# Powerboost.net
KiCad netlist of a schematic drawn in Altium Designer
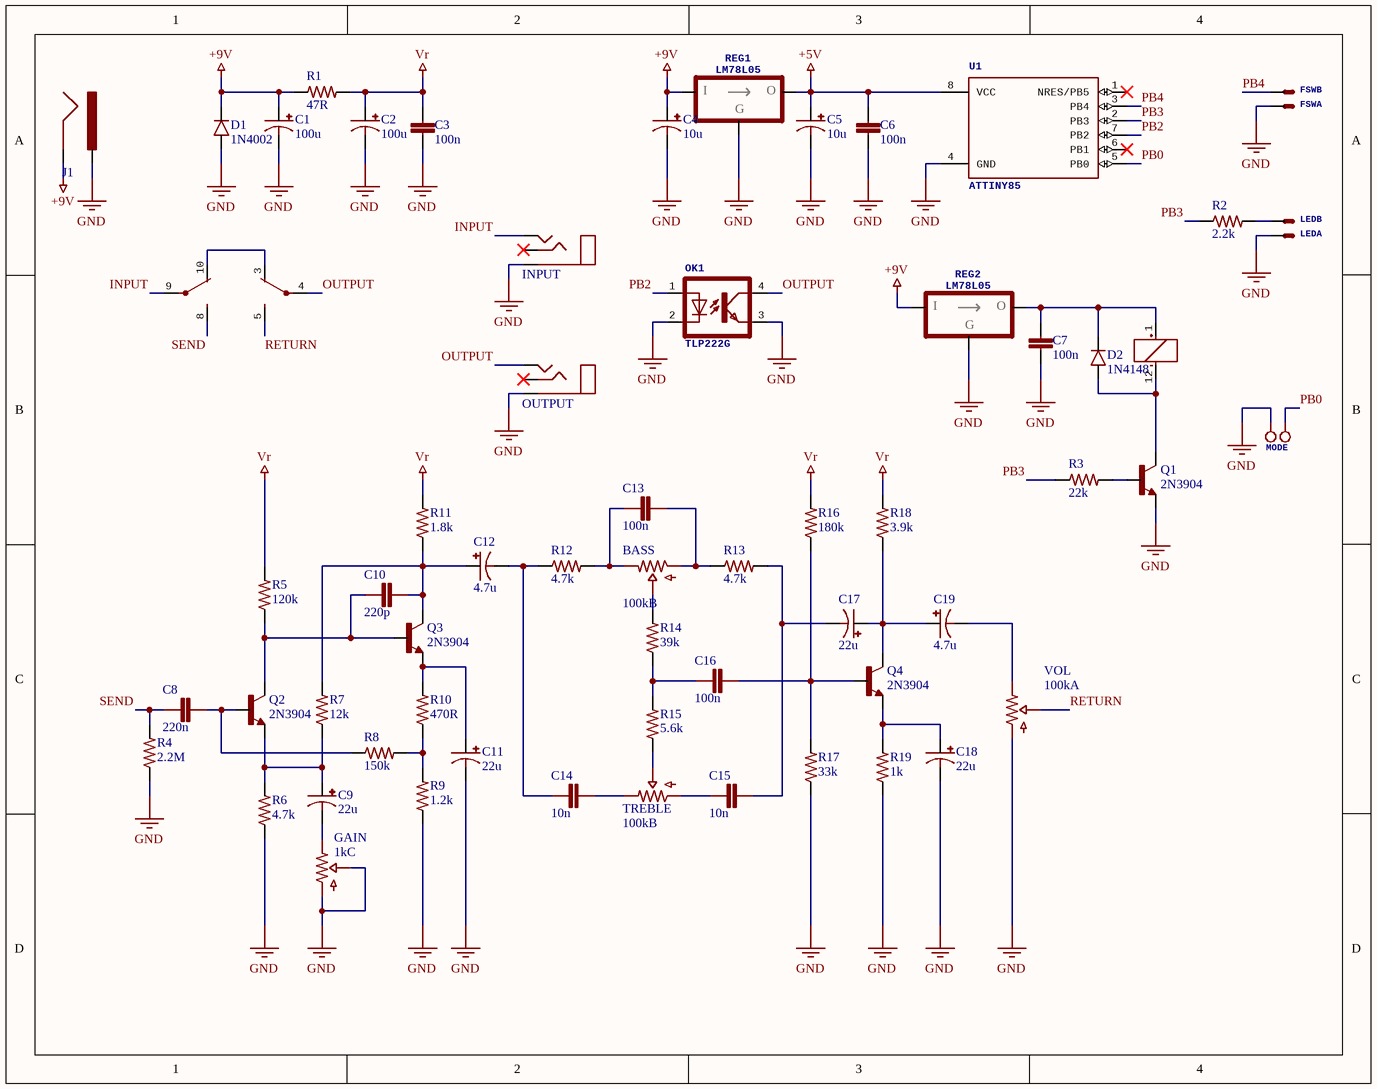
[diagram p0: Powerboost.SchDoc]

(export (version "E")
  (design (tool "Eeschema 10.0.6"))
  (components
    (comp (ref "BASS")
      (value "100kB")
      (footprint "ALPHA_16mm_BOTTOM")
      (description "100k Lin potentiometer round shaft")
      (libsource (lib "Pedals") (part "100kB_ALPHA_16mm"))
    )
    (comp (ref "C1")
      (value "100u")
      (footprint "ELEC_063_025")
      (description "100u 25V electrolytic capacitor")
      (libsource (lib "Pedals") (part "ELEC_100u_25V"))
    )
    (comp (ref "C2")
      (value "100u")
      (footprint "ELEC_063_025")
      (description "100u 25V electrolytic capacitor")
      (libsource (lib "Pedals") (part "ELEC_100u_25V"))
    )
    (comp (ref "C3")
      (value "100n")
      (footprint "CER_050")
      (description "100n MLCC X7R radial capacitor")
      (libsource (lib "") (part "CER_100n_1"))
    )
    (comp (ref "C4")
      (value "10u")
      (footprint "ELEC_040_020")
      (description "10u 50V electrolytic capacitor")
      (libsource (lib "Pedals") (part "ELEC_10u_50V"))
    )
    (comp (ref "C5")
      (value "10u")
      (footprint "ELEC_040_020")
      (description "10u 50V electrolytic capacitor")
      (libsource (lib "Pedals") (part "ELEC_10u_50V"))
    )
    (comp (ref "C6")
      (value "100n")
      (footprint "CER_050")
      (description "100n MLCC X7R radial capacitor")
      (libsource (lib "Pedals") (part "CER_100n"))
    )
    (comp (ref "C7")
      (value "100n")
      (footprint "CER_050")
      (description "100n MLCC X7R radial capacitor")
      (libsource (lib "") (part "CER_100n_1"))
    )
    (comp (ref "C8")
      (value "220n")
      (footprint "FILMBOX_SMALL")
      (description "220n 100V polyester film box capacitor")
      (libsource (lib "Pedals") (part "FILMBOX_220n"))
    )
    (comp (ref "C9")
      (value "22u")
      (footprint "ELEC_LESR_050_020")
      (description "22u 50V Low ESR ectrolytic capacitor")
      (libsource (lib "Pedals") (part "ELEC_LESR_22u_50V"))
    )
    (comp (ref "C10")
      (value "220p")
      (footprint "CER_050")
      (description "220p MLCC X7R radial capacitor")
      (libsource (lib "Pedals") (part "CER_220p"))
    )
    (comp (ref "C11")
      (value "22u")
      (footprint "ELEC_LESR_050_020")
      (description "22u 50V Low ESR ectrolytic capacitor")
      (libsource (lib "Pedals") (part "ELEC_LESR_22u_50V"))
    )
    (comp (ref "C12")
      (value "4.7u")
      (footprint "ELEC_LESR_050_020")
      (description "4.7u 50V Low ESR ectrolytic capacitor")
      (libsource (lib "Pedals") (part "ELEC_LESR_4.7u_50V"))
    )
    (comp (ref "C13")
      (value "100n")
      (footprint "FILMBOX_SMALL")
      (description "100n 100V polyester film box capacitor")
      (libsource (lib "Pedals") (part "FILMBOX_100n"))
    )
    (comp (ref "C14")
      (value "10n")
      (footprint "FILMBOX_SMALL")
      (description "10n 100V polyester film box capacitor")
      (libsource (lib "Pedals") (part "FILMBOX_10n"))
    )
    (comp (ref "C15")
      (value "10n")
      (footprint "FILMBOX_SMALL")
      (description "10n 100V polyester film box capacitor")
      (libsource (lib "Pedals") (part "FILMBOX_10n"))
    )
    (comp (ref "C16")
      (value "100n")
      (footprint "FILMBOX_SMALL")
      (description "100n 100V polyester film box capacitor")
      (libsource (lib "Pedals") (part "FILMBOX_100n"))
    )
    (comp (ref "C17")
      (value "22u")
      (footprint "ELEC_LESR_050_020")
      (description "22u 50V Low ESR ectrolytic capacitor")
      (libsource (lib "") (part "ELEC_LESR_22u_50V_1"))
    )
    (comp (ref "C18")
      (value "22u")
      (footprint "ELEC_LESR_050_020")
      (description "22u 50V Low ESR ectrolytic capacitor")
      (libsource (lib "Pedals") (part "ELEC_LESR_22u_50V"))
    )
    (comp (ref "C19")
      (value "4.7u")
      (footprint "ELEC_LESR_050_020")
      (description "4.7u 50V Low ESR ectrolytic capacitor")
      (libsource (lib "Pedals") (part "ELEC_LESR_4.7u_50V"))
    )
    (comp (ref "D1") (value "1N4002") (footprint "DO41_2") (libsource (lib "Pedals") (part "1N4002")))
    (comp (ref "D2") (value "1N4148") (footprint "DO35_2") (libsource (lib "Pedals") (part "1N4148")))
    (comp (ref "FSW")
      (value "~")
      (footprint "JST-XH-02")
      (description "2 Pins male XH header")
      (libsource (lib "Pedals") (part "JST-XH-02"))
    )
    (comp (ref "GAIN")
      (value "1kC")
      (footprint "ALPHA_16mm_BOTTOM")
      (description "1k Reverse log potentiometer round shaft")
      (libsource (lib "Pedals") (part "1kC_ALPHA_16mm"))
    )
    (comp (ref "INPUT")
      (value "~")
      (footprint "STEREO")
      (description "6.35mm stereo insulated socket jack PCB mounted")
      (libsource (lib "Pedals") (part "STEREO"))
    )
    (comp (ref "J1")
      (value "DC_JACK")
      (footprint "DC_JACK")
      (description "DC Power jack 2.1mm barrel")
      (libsource (lib "Pedals") (part "DC_JACK"))
    )
    (comp (ref "K1")
      (value "~")
      (footprint "NA5")
      (description "NA5W-K")
      (libsource (lib "") (part "NA5W-K_2"))
    )
    (comp (ref "LED")
      (value "JST-XH-02")
      (footprint "JST-XH-02")
      (description "2 Pins male XH header")
      (libsource (lib "Pedals") (part "JST-XH-02"))
    )
    (comp (ref "MODE")
      (value "HEADER_2PINS")
      (footprint "HEADER_2PINS")
      (description "2 Pins male header")
      (libsource (lib "Pedals") (part "HEADER_2PINS"))
    )
    (comp (ref "OK1") (value "TLP222G") (footprint "DIL4") (libsource (lib "Pedals") (part "TLP222G")))
    (comp (ref "OUTPUT")
      (value "~")
      (footprint "STEREO")
      (description "6.35mm stereo insulated socket jack PCB mounted")
      (libsource (lib "Pedals") (part "STEREO"))
    )
    (comp (ref "Q1") (value "2N3904") (footprint "TO92") (libsource (lib "Pedals") (part "2N3904")))
    (comp (ref "Q2") (value "2N3904") (footprint "TO92") (libsource (lib "Pedals") (part "2N3904")))
    (comp (ref "Q3") (value "2N3904") (footprint "TO92") (libsource (lib "Pedals") (part "2N3904")))
    (comp (ref "Q4") (value "2N3904") (footprint "TO92") (libsource (lib "Pedals") (part "2N3904")))
    (comp (ref "R1")
      (value "47R")
      (footprint "R_3_47R_025W")
      (description "47R metal film 1/4W Resistor")
      (libsource (lib "Pedals") (part "R_3_47R_025W"))
    )
    (comp (ref "R2")
      (value "2.2k")
      (footprint "R_3_2,2k_025W")
      (description "2.2k metal film 1/4W Resistor")
      (libsource (lib "Pedals") (part "R_3_2.2k_025W"))
    )
    (comp (ref "R3")
      (value "22k")
      (footprint "R_3_22k_025W")
      (description "22k metal film 1/4W Resistor")
      (libsource (lib "Pedals") (part "R_3_22k_025W"))
    )
    (comp (ref "R4")
      (value "2.2M")
      (footprint "R_3_2,2M_025W")
      (description "2.2M metal film 1/4W Resistor")
      (libsource (lib "Pedals") (part "R_3_2.2M_025W"))
    )
    (comp (ref "R5")
      (value "120k")
      (footprint "R_3_120k_025W")
      (description "120k metal film 1/4W Resistor")
      (libsource (lib "Pedals") (part "R_3_120k_025W"))
    )
    (comp (ref "R6")
      (value "4.7k")
      (footprint "R_3_4.7k_025W")
      (description "4.7kk metal film 1/4W Resistor")
      (libsource (lib "Pedals") (part "R_3_4.7k_025W"))
    )
    (comp (ref "R7")
      (value "12k")
      (footprint "R_3_12k_025W")
      (description "12k metal film 1/4W Resistor")
      (libsource (lib "Pedals") (part "R_3_12k_025W"))
    )
    (comp (ref "R8")
      (value "150k")
      (footprint "R_3_150k_025W")
      (description "150k metal film 1/4W Resistor")
      (libsource (lib "Pedals") (part "R_3_150k_025W"))
    )
    (comp (ref "R9")
      (value "1.2k")
      (footprint "R_3_1.2k_025W")
      (description "1.2k metal film 1/4W Resistor")
      (libsource (lib "Pedals") (part "R_3_1.2k_025W"))
    )
    (comp (ref "R10")
      (value "470R")
      (footprint "R_3_470R_025W")
      (description "470R metal film 1/4W Resistor")
      (libsource (lib "Pedals") (part "R_3_470R_025W"))
    )
    (comp (ref "R11")
      (value "1.8k")
      (footprint "R_3_1.8k_025W")
      (description "1.8k metal film 1/4W Resistor")
      (libsource (lib "Pedals") (part "R_3_1.8k_025W"))
    )
    (comp (ref "R12")
      (value "4.7k")
      (footprint "R_3_4.7k_025W")
      (description "4.7kk metal film 1/4W Resistor")
      (libsource (lib "Pedals") (part "R_3_4.7k_025W"))
    )
    (comp (ref "R13")
      (value "4.7k")
      (footprint "R_3_4.7k_025W")
      (description "4.7kk metal film 1/4W Resistor")
      (libsource (lib "Pedals") (part "R_3_4.7k_025W"))
    )
    (comp (ref "R14")
      (value "39k")
      (footprint "R_3_39k_025W")
      (description "39k metal film 1/4W Resistor")
      (libsource (lib "Pedals") (part "R_3_39k_025W"))
    )
    (comp (ref "R15")
      (value "5.6k")
      (footprint "R_3_5.6k_025W")
      (description "5.6k metal film 1/4W Resistor")
      (libsource (lib "Pedals") (part "R_3_5.6k_025W"))
    )
    (comp (ref "R16")
      (value "180k")
      (footprint "R_3_180k_025W")
      (description "180k metal film 1/4W Resistor")
      (libsource (lib "Pedals") (part "R_3_180k_025W"))
    )
    (comp (ref "R17")
      (value "33k")
      (footprint "R_3_33k_025W")
      (description "33k metal film 1/4W Resistor")
      (libsource (lib "Pedals") (part "R_3_33k_025W"))
    )
    (comp (ref "R18")
      (value "3.9k")
      (footprint "R_3_3.9k_025W")
      (description "3.9k metal film 1/4W Resistor")
      (libsource (lib "Pedals") (part "R_3_3.9k_025W"))
    )
    (comp (ref "R19")
      (value "1k")
      (footprint "R_3_1k_025W")
      (description "1k metal film 1/4W Resistor")
      (libsource (lib "Pedals") (part "R_3_1k_025W"))
    )
    (comp (ref "REG1")
      (value "LM78L05")
      (footprint "TO92")
      (description "78L05")
      (libsource (lib "Pedals") (part "LM78L05"))
    )
    (comp (ref "REG2")
      (value "LM78L05")
      (footprint "TO92")
      (description "78L05")
      (libsource (lib "Pedals") (part "LM78L05"))
    )
    (comp (ref "TREBLE")
      (value "100kB")
      (footprint "ALPHA_16mm_BOTTOM")
      (description "100k Lin potentiometer round shaft")
      (libsource (lib "Pedals") (part "100kB_ALPHA_16mm"))
    )
    (comp (ref "U1")
      (value "ATTINY85")
      (footprint "DIP8")
      (description "ATTINY85-20PU")
      (libsource (lib "Pedals") (part "ATTINY85"))
    )
    (comp (ref "VOL")
      (value "100kA")
      (footprint "ALPHA_16mm_BOTTOM")
      (description "100k Log potentiometer round shaft")
      (libsource (lib "Pedals") (part "100kA_ALPHA_16mm"))
    )
  )
  (nets
    (net (code "1") (name "+5V") (class "Default")
      (node (ref "C5") (pin "+") (pinfunction "+_+") (pintype "passive"))
      (node (ref "C6") (pin "2") (pinfunction "2_2") (pintype "passive"))
      (node (ref "REG1") (pin "3") (pinfunction "VO_3") (pintype "power_in"))
      (node (ref "U1") (pin "8") (pinfunction "VCC_8") (pintype "power_in"))
    )
    (net (code "2") (name "+9V") (class "Default")
      (node (ref "C1") (pin "+") (pinfunction "+_+") (pintype "passive"))
      (node (ref "C4") (pin "+") (pinfunction "+_+") (pintype "passive"))
      (node (ref "D1") (pin "C") (pinfunction "C_C") (pintype "passive"))
      (node (ref "J1") (pin "GND") (pinfunction "GND_GND") (pintype "passive"))
      (node (ref "R1") (pin "1") (pinfunction "1_1") (pintype "passive"))
      (node (ref "REG1") (pin "1") (pinfunction "VI_1") (pintype "power_in"))
      (node (ref "REG2") (pin "1") (pinfunction "VI_1") (pintype "power_in"))
    )
    (net (code "3") (name "/INPUT") (class "Default")
      (node (ref "INPUT") (pin "T") (pinfunction "T_T") (pintype "passive"))
      (node (ref "K1") (pin "9") (pinfunction "P_9") (pintype "passive"))
    )
    (net (code "4") (name "/OUTPUT") (class "Default")
      (node (ref "K1") (pin "4") (pinfunction "P_4") (pintype "passive"))
      (node (ref "OK1") (pin "4") (pinfunction "COL_4") (pintype "passive"))
      (node (ref "OUTPUT") (pin "T") (pinfunction "T_T") (pintype "passive"))
    )
    (net (code "5") (name "/PB0") (class "Default")
      (node (ref "MODE") (pin "2") (pinfunction "2_2") (pintype "passive"))
      (node (ref "U1") (pin "5") (pinfunction "PB0_5") (pintype "bidirectional"))
    )
    (net (code "6") (name "/PB2") (class "Default")
      (node (ref "OK1") (pin "1") (pinfunction "A_1") (pintype "passive"))
      (node (ref "U1") (pin "7") (pinfunction "PB2_7") (pintype "bidirectional"))
    )
    (net (code "7") (name "/PB3") (class "Default")
      (node (ref "R2") (pin "1") (pinfunction "1_1") (pintype "passive"))
      (node (ref "R3") (pin "1") (pinfunction "1_1") (pintype "passive"))
      (node (ref "U1") (pin "2") (pinfunction "PB3_2") (pintype "bidirectional"))
    )
    (net (code "8") (name "/PB4") (class "Default")
      (node (ref "FSW") (pin "1") (pinfunction "S_1") (pintype "passive"))
      (node (ref "U1") (pin "3") (pinfunction "PB4_3") (pintype "bidirectional"))
    )
    (net (code "9") (name "/RETURN") (class "Default")
      (node (ref "K1") (pin "5") (pinfunction "S_5") (pintype "passive"))
      (node (ref "VOL") (pin "2") (pinfunction "2_2") (pintype "passive"))
    )
    (net (code "10") (name "/SEND") (class "Default")
      (node (ref "C8") (pin "2") (pinfunction "2_2") (pintype "passive"))
      (node (ref "K1") (pin "8") (pinfunction "S_8") (pintype "passive"))
      (node (ref "R4") (pin "2") (pinfunction "2_2") (pintype "passive"))
    )
    (net (code "11") (name "GND") (class "Default")
      (node (ref "C1") (pin "-") (pinfunction "-_-") (pintype "passive"))
      (node (ref "C11") (pin "-") (pinfunction "-_-") (pintype "passive"))
      (node (ref "C18") (pin "-") (pinfunction "-_-") (pintype "passive"))
      (node (ref "C2") (pin "-") (pinfunction "-_-") (pintype "passive"))
      (node (ref "C3") (pin "2") (pinfunction "2_2") (pintype "passive"))
      (node (ref "C4") (pin "-") (pinfunction "-_-") (pintype "passive"))
      (node (ref "C5") (pin "-") (pinfunction "-_-") (pintype "passive"))
      (node (ref "C6") (pin "1") (pinfunction "1_1") (pintype "passive"))
      (node (ref "C7") (pin "2") (pinfunction "2_2") (pintype "passive"))
      (node (ref "D1") (pin "A") (pinfunction "A_A") (pintype "passive"))
      (node (ref "FSW") (pin "2") (pinfunction "S_2") (pintype "passive"))
      (node (ref "GAIN") (pin "1") (pinfunction "1_1") (pintype "passive"))
      (node (ref "GAIN") (pin "2") (pinfunction "2_2") (pintype "passive"))
      (node (ref "INPUT") (pin "S") (pinfunction "S_S") (pintype "passive"))
      (node (ref "J1") (pin "PWR") (pinfunction "PWR_PWR") (pintype "passive"))
      (node (ref "LED") (pin "2") (pinfunction "S_2") (pintype "passive"))
      (node (ref "MODE") (pin "1") (pinfunction "1_1") (pintype "passive"))
      (node (ref "OK1") (pin "2") (pinfunction "C_2") (pintype "passive"))
      (node (ref "OK1") (pin "3") (pinfunction "EMIT_3") (pintype "passive"))
      (node (ref "OUTPUT") (pin "S") (pinfunction "S_S") (pintype "passive"))
      (node (ref "Q1") (pin "3") (pinfunction "E_3") (pintype "passive"))
      (node (ref "R17") (pin "1") (pinfunction "1_1") (pintype "passive"))
      (node (ref "R19") (pin "1") (pinfunction "1_1") (pintype "passive"))
      (node (ref "R4") (pin "1") (pinfunction "1_1") (pintype "passive"))
      (node (ref "R6") (pin "1") (pinfunction "1_1") (pintype "passive"))
      (node (ref "R9") (pin "1") (pinfunction "1_1") (pintype "passive"))
      (node (ref "REG1") (pin "2") (pinfunction "GND_2") (pintype "power_in"))
      (node (ref "REG2") (pin "2") (pinfunction "GND_2") (pintype "power_in"))
      (node (ref "U1") (pin "4") (pinfunction "GND_4") (pintype "power_in"))
      (node (ref "VOL") (pin "1") (pinfunction "1_1") (pintype "passive"))
    )
    (net (code "12") (name "Net-(BASS-Pad1)") (class "Default")
      (node (ref "BASS") (pin "1") (pinfunction "1_1") (pintype "passive"))
      (node (ref "C13") (pin "1") (pinfunction "1_1") (pintype "passive"))
      (node (ref "R13") (pin "1") (pinfunction "1_1") (pintype "passive"))
    )
    (net (code "13") (name "Net-(BASS-Pad2)") (class "Default")
      (node (ref "BASS") (pin "2") (pinfunction "2_2") (pintype "passive"))
      (node (ref "R14") (pin "2") (pinfunction "2_2") (pintype "passive"))
    )
    (net (code "14") (name "Net-(BASS-Pad3)") (class "Default")
      (node (ref "BASS") (pin "3") (pinfunction "3_3") (pintype "passive"))
      (node (ref "C13") (pin "2") (pinfunction "2_2") (pintype "passive"))
      (node (ref "R12") (pin "2") (pinfunction "2_2") (pintype "passive"))
    )
    (net (code "15") (name "Net-(C9-Pad-)") (class "Default")
      (node (ref "C9") (pin "-") (pinfunction "-_-") (pintype "passive"))
      (node (ref "GAIN") (pin "3") (pinfunction "3_3") (pintype "passive"))
    )
    (net (code "16") (name "Net-(C12-Pad-)") (class "Default")
      (node (ref "C12") (pin "-") (pinfunction "-_-") (pintype "passive"))
      (node (ref "C14") (pin "2") (pinfunction "2_2") (pintype "passive"))
      (node (ref "R12") (pin "1") (pinfunction "1_1") (pintype "passive"))
    )
    (net (code "17") (name "Net-(C14-Pad1)") (class "Default")
      (node (ref "C14") (pin "1") (pinfunction "1_1") (pintype "passive"))
      (node (ref "TREBLE") (pin "3") (pinfunction "3_3") (pintype "passive"))
    )
    (net (code "18") (name "Net-(C15-Pad1)") (class "Default")
      (node (ref "C15") (pin "1") (pinfunction "1_1") (pintype "passive"))
      (node (ref "C17") (pin "-") (pinfunction "-_-") (pintype "passive"))
      (node (ref "R13") (pin "2") (pinfunction "2_2") (pintype "passive"))
    )
    (net (code "19") (name "Net-(C15-Pad2)") (class "Default")
      (node (ref "C15") (pin "2") (pinfunction "2_2") (pintype "passive"))
      (node (ref "TREBLE") (pin "1") (pinfunction "1_1") (pintype "passive"))
    )
    (net (code "20") (name "Net-(C16-Pad2)") (class "Default")
      (node (ref "C16") (pin "2") (pinfunction "2_2") (pintype "passive"))
      (node (ref "R14") (pin "1") (pinfunction "1_1") (pintype "passive"))
      (node (ref "R15") (pin "2") (pinfunction "2_2") (pintype "passive"))
    )
    (net (code "21") (name "Net-(C19-Pad-)") (class "Default")
      (node (ref "C19") (pin "-") (pinfunction "-_-") (pintype "passive"))
      (node (ref "VOL") (pin "3") (pinfunction "3_3") (pintype "passive"))
    )
    (net (code "22") (name "Net-(K1A-+)") (class "Default")
      (node (ref "C7") (pin "1") (pinfunction "1_1") (pintype "passive"))
      (node (ref "D2") (pin "C") (pinfunction "C_C") (pintype "passive"))
      (node (ref "K1") (pin "1") (pinfunction "+_1") (pintype "passive"))
      (node (ref "REG2") (pin "3") (pinfunction "VO_3") (pintype "power_in"))
    )
    (net (code "23") (name "Net-(K1A--)") (class "Default")
      (node (ref "D2") (pin "A") (pinfunction "A_A") (pintype "passive"))
      (node (ref "K1") (pin "12") (pinfunction "-_12") (pintype "passive"))
      (node (ref "Q1") (pin "1") (pinfunction "C_1") (pintype "passive"))
    )
    (net (code "24") (name "Net-(K1B-O)") (class "Default")
      (node (ref "K1") (pin "10") (pinfunction "O_10") (pintype "passive"))
      (node (ref "K1") (pin "3") (pinfunction "O_3") (pintype "passive"))
    )
    (net (code "25") (name "Net-(LEDB-S)") (class "Default")
      (node (ref "LED") (pin "1") (pinfunction "S_1") (pintype "passive"))
      (node (ref "R2") (pin "2") (pinfunction "2_2") (pintype "passive"))
    )
    (net (code "26") (name "Net-(Q1-B)") (class "Default")
      (node (ref "Q1") (pin "2") (pinfunction "B_2") (pintype "passive"))
      (node (ref "R3") (pin "2") (pinfunction "2_2") (pintype "passive"))
    )
    (net (code "27") (name "Net-(Q2-B)") (class "Default")
      (node (ref "C8") (pin "1") (pinfunction "1_1") (pintype "passive"))
      (node (ref "Q2") (pin "2") (pinfunction "B_2") (pintype "passive"))
      (node (ref "R8") (pin "1") (pinfunction "1_1") (pintype "passive"))
    )
    (net (code "28") (name "Net-(Q2-C)") (class "Default")
      (node (ref "C10") (pin "2") (pinfunction "2_2") (pintype "passive"))
      (node (ref "Q2") (pin "1") (pinfunction "C_1") (pintype "passive"))
      (node (ref "Q3") (pin "2") (pinfunction "B_2") (pintype "passive"))
      (node (ref "R5") (pin "1") (pinfunction "1_1") (pintype "passive"))
    )
    (net (code "29") (name "Net-(Q2-E)") (class "Default")
      (node (ref "C9") (pin "+") (pinfunction "+_+") (pintype "passive"))
      (node (ref "Q2") (pin "3") (pinfunction "E_3") (pintype "passive"))
      (node (ref "R6") (pin "2") (pinfunction "2_2") (pintype "passive"))
      (node (ref "R7") (pin "1") (pinfunction "1_1") (pintype "passive"))
    )
    (net (code "30") (name "Net-(Q3-C)") (class "Default")
      (node (ref "C10") (pin "1") (pinfunction "1_1") (pintype "passive"))
      (node (ref "C12") (pin "+") (pinfunction "+_+") (pintype "passive"))
      (node (ref "Q3") (pin "1") (pinfunction "C_1") (pintype "passive"))
      (node (ref "R11") (pin "1") (pinfunction "1_1") (pintype "passive"))
      (node (ref "R7") (pin "2") (pinfunction "2_2") (pintype "passive"))
    )
    (net (code "31") (name "Net-(Q3-E)") (class "Default")
      (node (ref "C11") (pin "+") (pinfunction "+_+") (pintype "passive"))
      (node (ref "Q3") (pin "3") (pinfunction "E_3") (pintype "passive"))
      (node (ref "R10") (pin "2") (pinfunction "2_2") (pintype "passive"))
    )
    (net (code "32") (name "Net-(Q4-B)") (class "Default")
      (node (ref "C16") (pin "1") (pinfunction "1_1") (pintype "passive"))
      (node (ref "Q4") (pin "2") (pinfunction "B_2") (pintype "passive"))
      (node (ref "R16") (pin "1") (pinfunction "1_1") (pintype "passive"))
      (node (ref "R17") (pin "2") (pinfunction "2_2") (pintype "passive"))
    )
    (net (code "33") (name "Net-(Q4-C)") (class "Default")
      (node (ref "C17") (pin "+") (pinfunction "+_+") (pintype "passive"))
      (node (ref "C19") (pin "+") (pinfunction "+_+") (pintype "passive"))
      (node (ref "Q4") (pin "1") (pinfunction "C_1") (pintype "passive"))
      (node (ref "R18") (pin "1") (pinfunction "1_1") (pintype "passive"))
    )
    (net (code "34") (name "Net-(Q4-E)") (class "Default")
      (node (ref "C18") (pin "+") (pinfunction "+_+") (pintype "passive"))
      (node (ref "Q4") (pin "3") (pinfunction "E_3") (pintype "passive"))
      (node (ref "R19") (pin "2") (pinfunction "2_2") (pintype "passive"))
    )
    (net (code "35") (name "Net-(R10-Pad1)") (class "Default")
      (node (ref "R10") (pin "1") (pinfunction "1_1") (pintype "passive"))
      (node (ref "R8") (pin "2") (pinfunction "2_2") (pintype "passive"))
      (node (ref "R9") (pin "2") (pinfunction "2_2") (pintype "passive"))
    )
    (net (code "36") (name "Net-(R15-Pad1)") (class "Default")
      (node (ref "R15") (pin "1") (pinfunction "1_1") (pintype "passive"))
      (node (ref "TREBLE") (pin "2") (pinfunction "2_2") (pintype "passive"))
    )
    (net (code "37") (name "Vr") (class "Default")
      (node (ref "C2") (pin "+") (pinfunction "+_+") (pintype "passive"))
      (node (ref "C3") (pin "1") (pinfunction "1_1") (pintype "passive"))
      (node (ref "R1") (pin "2") (pinfunction "2_2") (pintype "passive"))
      (node (ref "R11") (pin "2") (pinfunction "2_2") (pintype "passive"))
      (node (ref "R16") (pin "2") (pinfunction "2_2") (pintype "passive"))
      (node (ref "R18") (pin "2") (pinfunction "2_2") (pintype "passive"))
      (node (ref "R5") (pin "2") (pinfunction "2_2") (pintype "passive"))
    )
    (net (code "38") (name "unconnected-(INPUT-PadR)") (class "Default")
      (node (ref "INPUT") (pin "R") (pinfunction "R_R") (pintype "passive+no_connect"))
    )
    (net (code "39") (name "unconnected-(OUTPUT-PadR)") (class "Default")
      (node (ref "OUTPUT") (pin "R") (pinfunction "R_R") (pintype "passive+no_connect"))
    )
    (net (code "40") (name "unconnected-(U1-NRES{slash}PB5-Pad1)") (class "Default")
      (node (ref "U1") (pin "1") (pinfunction "NRES/PB5_1") (pintype "bidirectional+no_connect"))
    )
    (net (code "41") (name "unconnected-(U1-PB1-Pad6)") (class "Default")
      (node (ref "U1") (pin "6") (pinfunction "PB1_6") (pintype "bidirectional+no_connect"))
    )
  )
)
